# Transmitter.net
KiCad netlist of a schematic drawn in Altium Designer
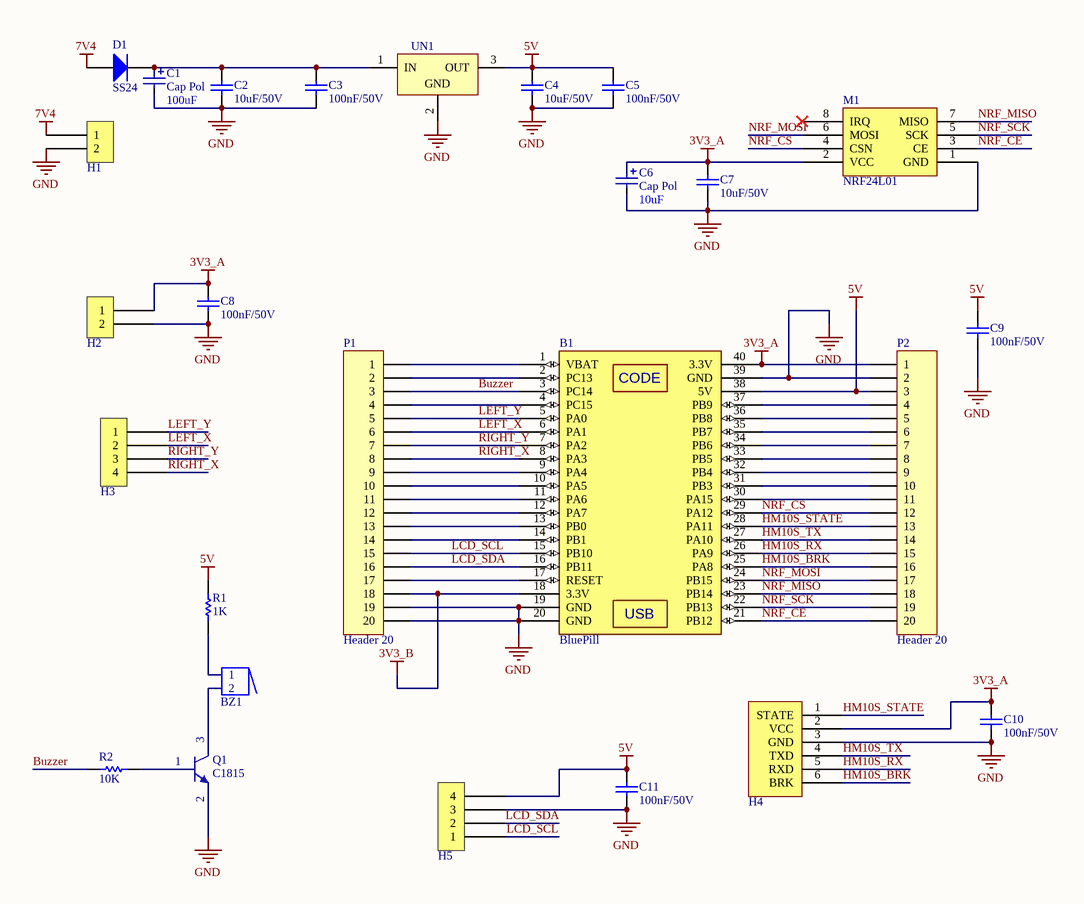
[diagram p0: Transmitter.SchDoc]

(export (version "E")
  (design (tool "Eeschema 10.0.6"))
  (components
    (comp (ref "B1") (value "BluePill") (footprint "BlUEPILL") (libsource (lib "Drone") (part "BluePill")))
    (comp (ref "BZ1") (value "Buzzer") (footprint "BUZZER") (libsource (lib "xecanbang") (part "Buzzer")))
    (comp (ref "C1")
      (value "Cap Pol")
      (footprint "CP1/2")
      (description "Polarized Capacitor (Radial)")
      (fields (field (name "ALTIUM_VALUE") "100uF"))
      (libsource (lib "Capacitor-TH") (part "Cap-TH-Pol"))
    )
    (comp (ref "C2")
      (value "10uF/50V")
      (footprint "CAP-SM-0805")
      (description "CAP CER 10UF 50V X5R 0805")
      (fields
        (field (name "MANUFACTURER") "Yageo")
        (field (name "MANUFACTURER PART NUMBER") "CC0805KKX5R9BB106")
      )
      (libsource (lib "Capacitor") (part "Cap-10uF-50V-0805"))
    )
    (comp (ref "C3")
      (value "100nF/50V")
      (footprint "CAP-SM-0805")
      (description "CAP CER 0.1UF 50V Y5V 0805")
      (fields
        (field (name "MANUFACTURER") "Samsung Electro-Mechanics")
        (field (name "MANUFACTURER PART NUMBER") "CL21F104ZBCNNNC")
      )
      (libsource (lib "Capacitor") (part "Cap-100nF-50V-0805"))
    )
    (comp (ref "C4")
      (value "10uF/50V")
      (footprint "CAP-SM-0805")
      (description "CAP CER 10UF 50V X5R 0805")
      (fields
        (field (name "MANUFACTURER") "Yageo")
        (field (name "MANUFACTURER PART NUMBER") "CC0805KKX5R9BB106")
      )
      (libsource (lib "Capacitor") (part "Cap-10uF-50V-0805"))
    )
    (comp (ref "C5")
      (value "100nF/50V")
      (footprint "CAP-SM-0805")
      (description "CAP CER 0.1UF 50V Y5V 0805")
      (fields
        (field (name "MANUFACTURER") "Samsung Electro-Mechanics")
        (field (name "MANUFACTURER PART NUMBER") "CL21F104ZBCNNNC")
      )
      (libsource (lib "Capacitor") (part "Cap-100nF-50V-0805"))
    )
    (comp (ref "C6")
      (value "Cap Pol")
      (footprint "CP1/2")
      (description "Polarized Capacitor (Radial)")
      (fields (field (name "ALTIUM_VALUE") "10uF"))
      (libsource (lib "Capacitor-TH") (part "Cap-TH-Pol"))
    )
    (comp (ref "C7")
      (value "10uF/50V")
      (footprint "CAP-SM-0805")
      (description "CAP CER 10UF 50V X5R 0805")
      (fields
        (field (name "MANUFACTURER") "Yageo")
        (field (name "MANUFACTURER PART NUMBER") "CC0805KKX5R9BB106")
      )
      (libsource (lib "Capacitor") (part "Cap-10uF-50V-0805"))
    )
    (comp (ref "C8")
      (value "100nF/50V")
      (footprint "CAP-SM-0805")
      (description "CAP CER 0.1UF 50V Y5V 0805")
      (fields
        (field (name "MANUFACTURER") "Samsung Electro-Mechanics")
        (field (name "MANUFACTURER PART NUMBER") "CL21F104ZBCNNNC")
      )
      (libsource (lib "Capacitor") (part "Cap-100nF-50V-0805"))
    )
    (comp (ref "C9")
      (value "100nF/50V")
      (footprint "CAP-SM-0805")
      (description "CAP CER 0.1UF 50V Y5V 0805")
      (fields
        (field (name "MANUFACTURER") "Samsung Electro-Mechanics")
        (field (name "MANUFACTURER PART NUMBER") "CL21F104ZBCNNNC")
      )
      (libsource (lib "Capacitor") (part "Cap-100nF-50V-0805"))
    )
    (comp (ref "C10")
      (value "100nF/50V")
      (footprint "CAP-SM-0805")
      (description "CAP CER 0.1UF 50V Y5V 0805")
      (fields
        (field (name "MANUFACTURER") "Samsung Electro-Mechanics")
        (field (name "MANUFACTURER PART NUMBER") "CL21F104ZBCNNNC")
      )
      (libsource (lib "Capacitor") (part "Cap-100nF-50V-0805"))
    )
    (comp (ref "C11")
      (value "100nF/50V")
      (footprint "CAP-SM-0805")
      (description "CAP CER 0.1UF 50V Y5V 0805")
      (fields
        (field (name "MANUFACTURER") "Samsung Electro-Mechanics")
        (field (name "MANUFACTURER PART NUMBER") "CL21F104ZBCNNNC")
      )
      (libsource (lib "Capacitor") (part "Cap-100nF-50V-0805"))
    )
    (comp (ref "D1")
      (value "SS24")
      (footprint "SS24")
      (description "DIODE SCHOTTKY 40V 2A DO214AA")
      (fields (field (name "MANUFACTURER") "ON Semiconductor"))
      (libsource (lib "Diode") (part "Diode-SS24"))
    )
    (comp (ref "H1") (value "XH B2B") (footprint "XH B2B") (libsource (lib "") (part "XH B2B_1")))
    (comp (ref "H2") (value "XH B2B") (footprint "XH B2B") (libsource (lib "Drone") (part "XH B2B")))
    (comp (ref "H3") (value "XHB4B") (footprint "XHB4B") (libsource (lib "Drone") (part "XH B4B")))
    (comp (ref "H4")
      (value "HC-05-06-TH")
      (footprint "HM-10S CC2541")
      (fields (field (name "LOCAL SUPPLIER PART NUMBER") "HS000882"))
      (libsource (lib "Drone") (part "HM-10S CC2541"))
    )
    (comp (ref "H5") (value "XHB4B") (footprint "XHB4B") (libsource (lib "") (part "XH B4B_1")))
    (comp (ref "M1")
      (value "NRF24L01")
      (footprint "NRF24L01")
      (fields (field (name "LOCAL SUPPLIER PART NUMBER") "HS000888"))
      (libsource (lib "Drone") (part "NRF24L01"))
    )
    (comp (ref "P1")
      (value "Header 20")
      (footprint "HDR1X20")
      (description "Header, 20-Pin")
      (fields (field (name "PUBLISHER") "Altium Limited"))
      (libsource (lib "") (part "Header 20_1"))
    )
    (comp (ref "P2")
      (value "Header 20")
      (footprint "HDR1X20")
      (description "Header, 20-Pin")
      (fields (field (name "PUBLISHER") "Altium Limited"))
      (libsource (lib "Miscellaneous Connectors") (part "Header 20"))
    )
    (comp (ref "Q1") (value "C1815") (footprint "QTO-92") (libsource (lib "BJT") (part "C1815")))
    (comp (ref "R1")
      (value "1K")
      (footprint "Resistor:RES-SM-0805")
      (description "RES 1K OHM 1% 1/4W 0805")
      (fields
        (field (name "MANUFACTURER") "Stackpole Electronics Inc")
        (field (name "MANUFACTURER PART NUMBER") "RNCP0805FTD1K00")
      )
      (libsource (lib "Resistor") (part "Res-1K-0805"))
    )
    (comp (ref "R2")
      (value "10K")
      (footprint "Resistor:RES-SM-0805")
      (description "RES 10K OHM 1% 1/4W 0805")
      (fields
        (field (name "MANUFACTURER") "Stackpole Electronics Inc")
        (field (name "MANUFACTURER PART NUMBER") "RNCP0805FTD10K0")
      )
      (libsource (lib "Resistor") (part "Res-10k-0805"))
    )
    (comp (ref "UN1")
      (value "LM7805")
      (footprint "QTO-220")
      (description "Positive Voltage Regulator")
      (libsource (lib "PIF_Library") (part "LM7805"))
    )
  )
  (nets
    (net (code "1") (name "/Buzzer") (class "Default")
      (node (ref "B1") (pin "3") (pinfunction "PC14_3") (pintype "bidirectional"))
      (node (ref "P1") (pin "3") (pinfunction "3_3") (pintype "passive"))
      (node (ref "R2") (pin "1") (pinfunction "1_1") (pintype "passive"))
    )
    (net (code "2") (name "/HM10S_BRK") (class "Default")
      (node (ref "B1") (pin "25") (pinfunction "PA8_25") (pintype "bidirectional"))
      (node (ref "H4") (pin "6") (pinfunction "BRK_6") (pintype "passive"))
      (node (ref "P2") (pin "16") (pinfunction "16_16") (pintype "passive"))
    )
    (net (code "3") (name "/HM10S_RX") (class "Default")
      (node (ref "B1") (pin "26") (pinfunction "PA9_26") (pintype "bidirectional"))
      (node (ref "H4") (pin "5") (pinfunction "RXD_5") (pintype "passive"))
      (node (ref "P2") (pin "15") (pinfunction "15_15") (pintype "passive"))
    )
    (net (code "4") (name "/HM10S_STATE") (class "Default")
      (node (ref "B1") (pin "28") (pinfunction "PA11_28") (pintype "bidirectional"))
      (node (ref "H4") (pin "1") (pinfunction "STATE_1") (pintype "passive"))
      (node (ref "P2") (pin "13") (pinfunction "13_13") (pintype "passive"))
    )
    (net (code "5") (name "/HM10S_TX") (class "Default")
      (node (ref "B1") (pin "27") (pinfunction "PA10_27") (pintype "bidirectional"))
      (node (ref "H4") (pin "4") (pinfunction "TXD_4") (pintype "passive"))
      (node (ref "P2") (pin "14") (pinfunction "14_14") (pintype "passive"))
    )
    (net (code "6") (name "/LCD_SCL") (class "Default")
      (node (ref "B1") (pin "15") (pinfunction "PB10_15") (pintype "bidirectional"))
      (node (ref "H5") (pin "1") (pinfunction "1_1") (pintype "passive"))
      (node (ref "P1") (pin "15") (pinfunction "15_15") (pintype "passive"))
    )
    (net (code "7") (name "/LCD_SDA") (class "Default")
      (node (ref "B1") (pin "16") (pinfunction "PB11_16") (pintype "bidirectional"))
      (node (ref "H5") (pin "2") (pinfunction "2_2") (pintype "passive"))
      (node (ref "P1") (pin "16") (pinfunction "16_16") (pintype "passive"))
    )
    (net (code "8") (name "/LEFT_X") (class "Default")
      (node (ref "B1") (pin "6") (pinfunction "PA1_6") (pintype "bidirectional"))
      (node (ref "H3") (pin "2") (pinfunction "2_2") (pintype "passive"))
      (node (ref "P1") (pin "6") (pinfunction "6_6") (pintype "passive"))
    )
    (net (code "9") (name "/LEFT_Y") (class "Default")
      (node (ref "B1") (pin "5") (pinfunction "PA0_5") (pintype "bidirectional"))
      (node (ref "H3") (pin "1") (pinfunction "1_1") (pintype "passive"))
      (node (ref "P1") (pin "5") (pinfunction "5_5") (pintype "passive"))
    )
    (net (code "10") (name "/NRF_CE") (class "Default")
      (node (ref "B1") (pin "21") (pinfunction "PB12_21") (pintype "bidirectional"))
      (node (ref "M1") (pin "3") (pinfunction "CE_3") (pintype "passive"))
      (node (ref "P2") (pin "20") (pinfunction "20_20") (pintype "passive"))
    )
    (net (code "11") (name "/NRF_CS") (class "Default")
      (node (ref "B1") (pin "29") (pinfunction "PA12_29") (pintype "bidirectional"))
      (node (ref "M1") (pin "4") (pinfunction "CSN_4") (pintype "passive"))
      (node (ref "P2") (pin "12") (pinfunction "12_12") (pintype "passive"))
    )
    (net (code "12") (name "/NRF_MISO") (class "Default")
      (node (ref "B1") (pin "23") (pinfunction "PB14_23") (pintype "bidirectional"))
      (node (ref "M1") (pin "7") (pinfunction "MISO_7") (pintype "passive"))
      (node (ref "P2") (pin "18") (pinfunction "18_18") (pintype "passive"))
    )
    (net (code "13") (name "/NRF_MOSI") (class "Default")
      (node (ref "B1") (pin "24") (pinfunction "PB15_24") (pintype "bidirectional"))
      (node (ref "M1") (pin "6") (pinfunction "MOSI_6") (pintype "passive"))
      (node (ref "P2") (pin "17") (pinfunction "17_17") (pintype "passive"))
    )
    (net (code "14") (name "/NRF_SCK") (class "Default")
      (node (ref "B1") (pin "22") (pinfunction "PB13_22") (pintype "bidirectional"))
      (node (ref "M1") (pin "5") (pinfunction "SCK_5") (pintype "passive"))
      (node (ref "P2") (pin "19") (pinfunction "19_19") (pintype "passive"))
    )
    (net (code "15") (name "/RIGHT_X") (class "Default")
      (node (ref "B1") (pin "8") (pinfunction "PA3_8") (pintype "bidirectional"))
      (node (ref "H3") (pin "4") (pinfunction "4_4") (pintype "passive"))
      (node (ref "P1") (pin "8") (pinfunction "8_8") (pintype "passive"))
    )
    (net (code "16") (name "/RIGHT_Y") (class "Default")
      (node (ref "B1") (pin "7") (pinfunction "PA2_7") (pintype "bidirectional"))
      (node (ref "H3") (pin "3") (pinfunction "3_3") (pintype "passive"))
      (node (ref "P1") (pin "7") (pinfunction "7_7") (pintype "passive"))
    )
    (net (code "17") (name "3V3_A") (class "Default")
      (node (ref "B1") (pin "40") (pinfunction "3.3V_40") (pintype "power_in"))
      (node (ref "C10") (pin "1") (pinfunction "1_1") (pintype "passive"))
      (node (ref "C6") (pin "1") (pinfunction "1_1") (pintype "passive"))
      (node (ref "C7") (pin "2") (pinfunction "2_2") (pintype "passive"))
      (node (ref "C8") (pin "2") (pinfunction "2_2") (pintype "passive"))
      (node (ref "H2") (pin "1") (pinfunction "1_1") (pintype "passive"))
      (node (ref "H4") (pin "2") (pinfunction "VCC_2") (pintype "passive"))
      (node (ref "M1") (pin "2") (pinfunction "VCC_2") (pintype "passive"))
      (node (ref "P2") (pin "1") (pinfunction "1_1") (pintype "passive"))
    )
    (net (code "18") (name "3V3_B") (class "Default")
      (node (ref "B1") (pin "18") (pinfunction "3.3V_18") (pintype "power_in"))
      (node (ref "P1") (pin "18") (pinfunction "18_18") (pintype "passive"))
    )
    (net (code "19") (name "5V") (class "Default")
      (node (ref "B1") (pin "38") (pinfunction "5V_38") (pintype "power_in"))
      (node (ref "C11") (pin "2") (pinfunction "2_2") (pintype "passive"))
      (node (ref "C4") (pin "2") (pinfunction "2_2") (pintype "passive"))
      (node (ref "C5") (pin "2") (pinfunction "2_2") (pintype "passive"))
      (node (ref "C9") (pin "1") (pinfunction "1_1") (pintype "passive"))
      (node (ref "H5") (pin "4") (pinfunction "4_4") (pintype "passive"))
      (node (ref "P2") (pin "3") (pinfunction "3_3") (pintype "passive"))
      (node (ref "R1") (pin "2") (pinfunction "2_2") (pintype "passive"))
      (node (ref "UN1") (pin "3") (pinfunction "OUT_3") (pintype "power_in"))
    )
    (net (code "20") (name "7V4") (class "Default")
      (node (ref "D1") (pin "2") (pinfunction "A_2") (pintype "passive"))
      (node (ref "H1") (pin "1") (pinfunction "1_1") (pintype "passive"))
    )
    (net (code "21") (name "GND") (class "Default")
      (node (ref "B1") (pin "19") (pinfunction "GND_19") (pintype "power_in"))
      (node (ref "B1") (pin "20") (pinfunction "GND_20") (pintype "power_in"))
      (node (ref "B1") (pin "39") (pinfunction "GND_39") (pintype "power_in"))
      (node (ref "C1") (pin "2") (pinfunction "2_2") (pintype "passive"))
      (node (ref "C10") (pin "2") (pinfunction "2_2") (pintype "passive"))
      (node (ref "C11") (pin "1") (pinfunction "1_1") (pintype "passive"))
      (node (ref "C2") (pin "1") (pinfunction "1_1") (pintype "passive"))
      (node (ref "C3") (pin "1") (pinfunction "1_1") (pintype "passive"))
      (node (ref "C4") (pin "1") (pinfunction "1_1") (pintype "passive"))
      (node (ref "C5") (pin "1") (pinfunction "1_1") (pintype "passive"))
      (node (ref "C6") (pin "2") (pinfunction "2_2") (pintype "passive"))
      (node (ref "C7") (pin "1") (pinfunction "1_1") (pintype "passive"))
      (node (ref "C8") (pin "1") (pinfunction "1_1") (pintype "passive"))
      (node (ref "C9") (pin "2") (pinfunction "2_2") (pintype "passive"))
      (node (ref "H1") (pin "2") (pinfunction "2_2") (pintype "passive"))
      (node (ref "H2") (pin "2") (pinfunction "2_2") (pintype "passive"))
      (node (ref "H4") (pin "3") (pinfunction "GND_3") (pintype "passive"))
      (node (ref "H5") (pin "3") (pinfunction "3_3") (pintype "passive"))
      (node (ref "M1") (pin "1") (pinfunction "GND_1") (pintype "passive"))
      (node (ref "P1") (pin "19") (pinfunction "19_19") (pintype "passive"))
      (node (ref "P1") (pin "20") (pinfunction "20_20") (pintype "passive"))
      (node (ref "P2") (pin "2") (pinfunction "2_2") (pintype "passive"))
      (node (ref "Q1") (pin "2") (pinfunction "E_2") (pintype "passive"))
      (node (ref "UN1") (pin "2") (pinfunction "GND_2") (pintype "power_in"))
    )
    (net (code "22") (name "Net-(B1-PA4)") (class "Default")
      (node (ref "B1") (pin "9") (pinfunction "PA4_9") (pintype "bidirectional"))
      (node (ref "P1") (pin "9") (pinfunction "9_9") (pintype "passive"))
    )
    (net (code "23") (name "Net-(B1-PA5)") (class "Default")
      (node (ref "B1") (pin "10") (pinfunction "PA5_10") (pintype "bidirectional"))
      (node (ref "P1") (pin "10") (pinfunction "10_10") (pintype "passive"))
    )
    (net (code "24") (name "Net-(B1-PA6)") (class "Default")
      (node (ref "B1") (pin "11") (pinfunction "PA6_11") (pintype "bidirectional"))
      (node (ref "P1") (pin "11") (pinfunction "11_11") (pintype "passive"))
    )
    (net (code "25") (name "Net-(B1-PA7)") (class "Default")
      (node (ref "B1") (pin "12") (pinfunction "PA7_12") (pintype "bidirectional"))
      (node (ref "P1") (pin "12") (pinfunction "12_12") (pintype "passive"))
    )
    (net (code "26") (name "Net-(B1-PA15)") (class "Default")
      (node (ref "B1") (pin "30") (pinfunction "PA15_30") (pintype "bidirectional"))
      (node (ref "P2") (pin "11") (pinfunction "11_11") (pintype "passive"))
    )
    (net (code "27") (name "Net-(B1-PB0)") (class "Default")
      (node (ref "B1") (pin "13") (pinfunction "PB0_13") (pintype "bidirectional"))
      (node (ref "P1") (pin "13") (pinfunction "13_13") (pintype "passive"))
    )
    (net (code "28") (name "Net-(B1-PB1)") (class "Default")
      (node (ref "B1") (pin "14") (pinfunction "PB1_14") (pintype "bidirectional"))
      (node (ref "P1") (pin "14") (pinfunction "14_14") (pintype "passive"))
    )
    (net (code "29") (name "Net-(B1-PB3)") (class "Default")
      (node (ref "B1") (pin "31") (pinfunction "PB3_31") (pintype "bidirectional"))
      (node (ref "P2") (pin "10") (pinfunction "10_10") (pintype "passive"))
    )
    (net (code "30") (name "Net-(B1-PB4)") (class "Default")
      (node (ref "B1") (pin "32") (pinfunction "PB4_32") (pintype "bidirectional"))
      (node (ref "P2") (pin "9") (pinfunction "9_9") (pintype "passive"))
    )
    (net (code "31") (name "Net-(B1-PB5)") (class "Default")
      (node (ref "B1") (pin "33") (pinfunction "PB5_33") (pintype "bidirectional"))
      (node (ref "P2") (pin "8") (pinfunction "8_8") (pintype "passive"))
    )
    (net (code "32") (name "Net-(B1-PB6)") (class "Default")
      (node (ref "B1") (pin "34") (pinfunction "PB6_34") (pintype "bidirectional"))
      (node (ref "P2") (pin "7") (pinfunction "7_7") (pintype "passive"))
    )
    (net (code "33") (name "Net-(B1-PB7)") (class "Default")
      (node (ref "B1") (pin "35") (pinfunction "PB7_35") (pintype "bidirectional"))
      (node (ref "P2") (pin "6") (pinfunction "6_6") (pintype "passive"))
    )
    (net (code "34") (name "Net-(B1-PB8)") (class "Default")
      (node (ref "B1") (pin "36") (pinfunction "PB8_36") (pintype "bidirectional"))
      (node (ref "P2") (pin "5") (pinfunction "5_5") (pintype "passive"))
    )
    (net (code "35") (name "Net-(B1-PB9)") (class "Default")
      (node (ref "B1") (pin "37") (pinfunction "PB9_37") (pintype "bidirectional"))
      (node (ref "P2") (pin "4") (pinfunction "4_4") (pintype "passive"))
    )
    (net (code "36") (name "Net-(B1-PC13)") (class "Default")
      (node (ref "B1") (pin "2") (pinfunction "PC13_2") (pintype "bidirectional"))
      (node (ref "P1") (pin "2") (pinfunction "2_2") (pintype "passive"))
    )
    (net (code "37") (name "Net-(B1-PC15)") (class "Default")
      (node (ref "B1") (pin "4") (pinfunction "PC15_4") (pintype "bidirectional"))
      (node (ref "P1") (pin "4") (pinfunction "4_4") (pintype "passive"))
    )
    (net (code "38") (name "Net-(B1-RESET)") (class "Default")
      (node (ref "B1") (pin "17") (pinfunction "RESET_17") (pintype "bidirectional"))
      (node (ref "P1") (pin "17") (pinfunction "17_17") (pintype "passive"))
    )
    (net (code "39") (name "Net-(B1-VBAT)") (class "Default")
      (node (ref "B1") (pin "1") (pinfunction "VBAT_1") (pintype "bidirectional"))
      (node (ref "P1") (pin "1") (pinfunction "1_1") (pintype "passive"))
    )
    (net (code "40") (name "Net-(BZ1-Pad1)") (class "Default")
      (node (ref "BZ1") (pin "1") (pinfunction "1_1") (pintype "passive"))
      (node (ref "R1") (pin "1") (pinfunction "1_1") (pintype "passive"))
    )
    (net (code "41") (name "Net-(D1-K)") (class "Default")
      (node (ref "C1") (pin "1") (pinfunction "1_1") (pintype "passive"))
      (node (ref "C2") (pin "2") (pinfunction "2_2") (pintype "passive"))
      (node (ref "C3") (pin "2") (pinfunction "2_2") (pintype "passive"))
      (node (ref "D1") (pin "1") (pinfunction "K_1") (pintype "passive"))
      (node (ref "UN1") (pin "1") (pinfunction "IN_1") (pintype "power_in"))
    )
    (net (code "42") (name "Net-(Q1-B)") (class "Default")
      (node (ref "Q1") (pin "1") (pinfunction "B_1") (pintype "passive"))
      (node (ref "R2") (pin "2") (pinfunction "2_2") (pintype "passive"))
    )
    (net (code "43") (name "Net-(Q1-C)") (class "Default")
      (node (ref "BZ1") (pin "2") (pinfunction "2_2") (pintype "passive"))
      (node (ref "Q1") (pin "3") (pinfunction "C_3") (pintype "passive"))
    )
    (net (code "44") (name "unconnected-(M1-IRQ-Pad8)") (class "Default")
      (node (ref "M1") (pin "8") (pinfunction "IRQ_8") (pintype "passive+no_connect"))
    )
  )
)
